# GateDriver.net
KiCad netlist of a schematic drawn in Altium Designer
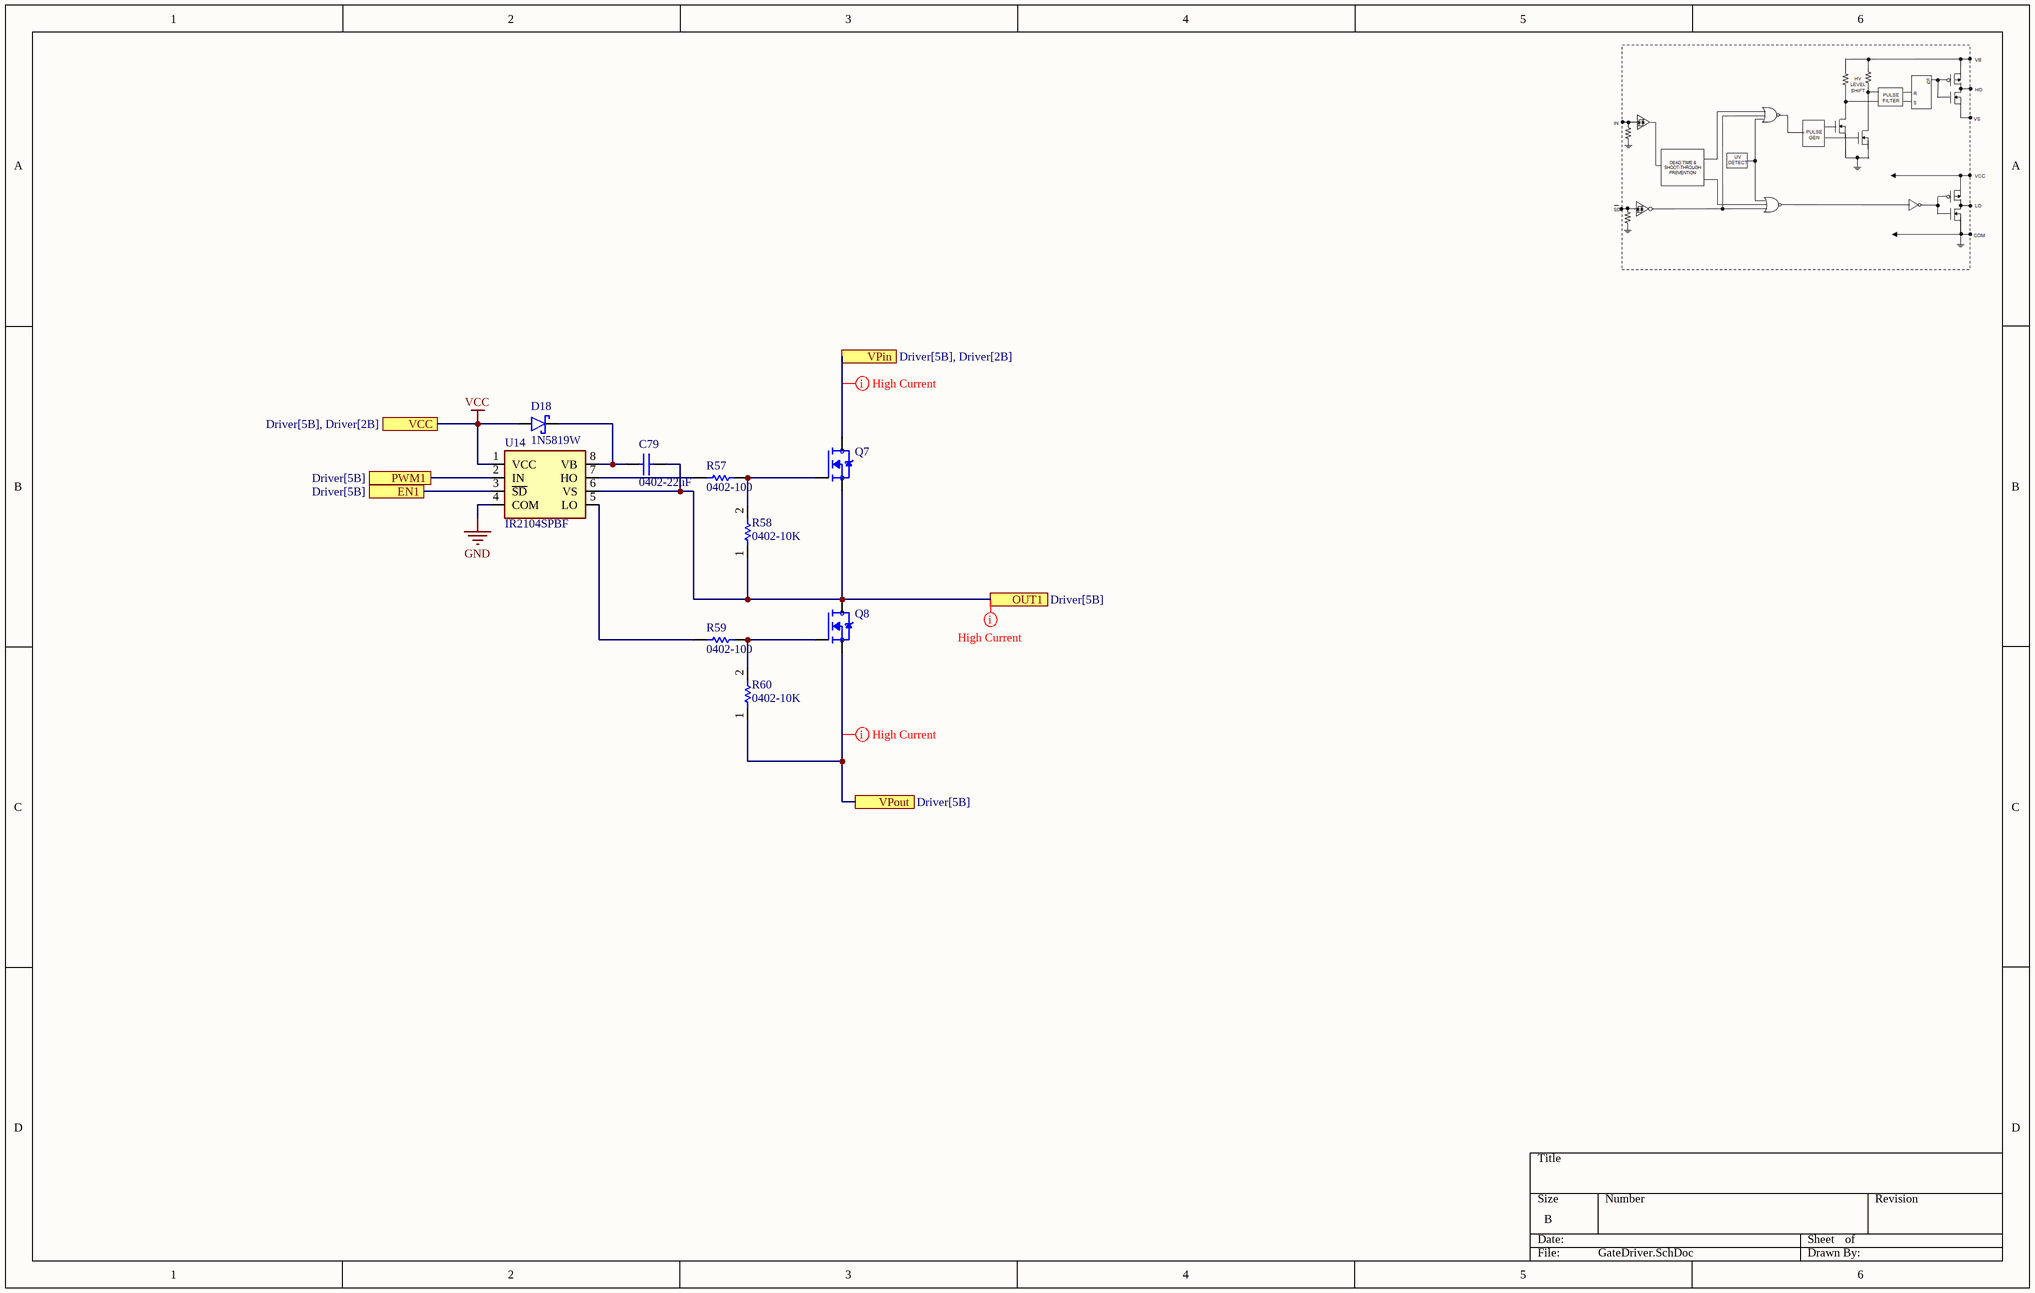
[diagram p0: GateDriver.SchDoc]

(export (version "E")
  (design (tool "Eeschema 10.0.6"))
  (components
    (comp (ref "C79")
      (value "0402-22uF")
      (footprint "CAPC0402(1005)60_N")
      (description "Capacitor 22uF 0402")
      (fields (field (name "TOLERANCE") "20%"))
      (libsource (lib "") (part "0402_2"))
    )
    (comp (ref "D18") (value "1N5819W") (footprint "1N5819W") (libsource (lib "Tin Tran") (part "1N5819W")))
    (comp (ref "Q7")
      (value "IRLR7843TRPBF")
      (footprint "TO229P990X239-3_4N")
      (description "RoHS Compliant")
      (fields (field (name "MF") "Infineon Technologies"))
      (libsource (lib "Tin Tran") (part "IRLR7843TRPBF"))
    )
    (comp (ref "Q8")
      (value "IRLR7843TRPBF")
      (footprint "TO229P990X239-3_4N")
      (description "RoHS Compliant")
      (fields (field (name "MF") "Infineon Technologies"))
      (libsource (lib "Tin Tran") (part "IRLR7843TRPBF"))
    )
    (comp (ref "R57")
      (value "0402-100")
      (footprint "R-0402-1K")
      (description "0402Resistor 100Ohm")
      (libsource (lib "") (part "0402_1"))
    )
    (comp (ref "R58")
      (value "0402-10K")
      (footprint "R-0402-10K")
      (description "RES 0402 10K")
      (libsource (lib "Tin Tran") (part "0402"))
    )
    (comp (ref "R59")
      (value "0402-100")
      (footprint "R-0402-1K")
      (description "0402Resistor 100Ohm")
      (libsource (lib "") (part "0402_1"))
    )
    (comp (ref "R60")
      (value "0402-10K")
      (footprint "R-0402-10K")
      (description "RES 0402 10K")
      (libsource (lib "Tin Tran") (part "0402"))
    )
    (comp (ref "U14")
      (value "IR2104SPBF")
      (footprint "IR2104SPBF")
      (description "Half-Bridge Gate Driver IC Non-Inverting 8-SOIC")
      (fields (field (name "MF") "Infineon"))
      (libsource (lib "Tin Tran") (part "IR2104SPBF"))
    )
  )
  (nets
    (net (code "1") (name "/EN1") (class "Default")
      (node (ref "U14") (pin "3") (pinfunction "~{SD}_3") (pintype "bidirectional"))
    )
    (net (code "2") (name "/OUT1") (class "Default")
      (node (ref "C79") (pin "2") (pinfunction "2_2") (pintype "passive"))
      (node (ref "Q7") (pin "3") (pinfunction "S_3") (pintype "passive"))
      (node (ref "Q8") (pin "4") (pinfunction "D_4") (pintype "passive"))
      (node (ref "R58") (pin "1") (pinfunction "1_1") (pintype "passive"))
      (node (ref "U14") (pin "6") (pinfunction "VS_6") (pintype "bidirectional"))
    )
    (net (code "3") (name "/PWM1") (class "Default")
      (node (ref "U14") (pin "2") (pinfunction "IN_2") (pintype "bidirectional"))
    )
    (net (code "4") (name "/VPin") (class "Default")
      (node (ref "Q7") (pin "4") (pinfunction "D_4") (pintype "passive"))
    )
    (net (code "5") (name "/VPout") (class "Default")
      (node (ref "Q8") (pin "3") (pinfunction "S_3") (pintype "passive"))
      (node (ref "R60") (pin "1") (pinfunction "1_1") (pintype "passive"))
    )
    (net (code "6") (name "GND") (class "Default")
      (node (ref "U14") (pin "4") (pinfunction "COM_4") (pintype "bidirectional"))
    )
    (net (code "7") (name "Net-(Q7-G)") (class "Default")
      (node (ref "Q7") (pin "1") (pinfunction "G_1") (pintype "passive"))
      (node (ref "R57") (pin "2") (pinfunction "2_2") (pintype "passive"))
      (node (ref "R58") (pin "2") (pinfunction "2_2") (pintype "passive"))
    )
    (net (code "8") (name "Net-(Q8-G)") (class "Default")
      (node (ref "Q8") (pin "1") (pinfunction "G_1") (pintype "passive"))
      (node (ref "R59") (pin "2") (pinfunction "2_2") (pintype "passive"))
      (node (ref "R60") (pin "2") (pinfunction "2_2") (pintype "passive"))
    )
    (net (code "9") (name "Net-(U14-HO)") (class "Default")
      (node (ref "R57") (pin "1") (pinfunction "1_1") (pintype "passive"))
      (node (ref "U14") (pin "7") (pinfunction "HO_7") (pintype "bidirectional"))
    )
    (net (code "10") (name "Net-(U14-LO)") (class "Default")
      (node (ref "R59") (pin "1") (pinfunction "1_1") (pintype "passive"))
      (node (ref "U14") (pin "5") (pinfunction "LO_5") (pintype "bidirectional"))
    )
    (net (code "11") (name "Net-(U14-VB)") (class "Default")
      (node (ref "C79") (pin "1") (pinfunction "1_1") (pintype "passive"))
      (node (ref "D18") (pin "K") (pinfunction "K_K") (pintype "passive"))
      (node (ref "U14") (pin "8") (pinfunction "VB_8") (pintype "bidirectional"))
    )
    (net (code "12") (name "VCC") (class "Default")
      (node (ref "D18") (pin "A") (pinfunction "A_A") (pintype "passive"))
      (node (ref "U14") (pin "1") (pinfunction "VCC_1") (pintype "bidirectional"))
    )
  )
)
